# RHB0032E_pac.net
KiCad netlist of a schematic drawn in EAGLE
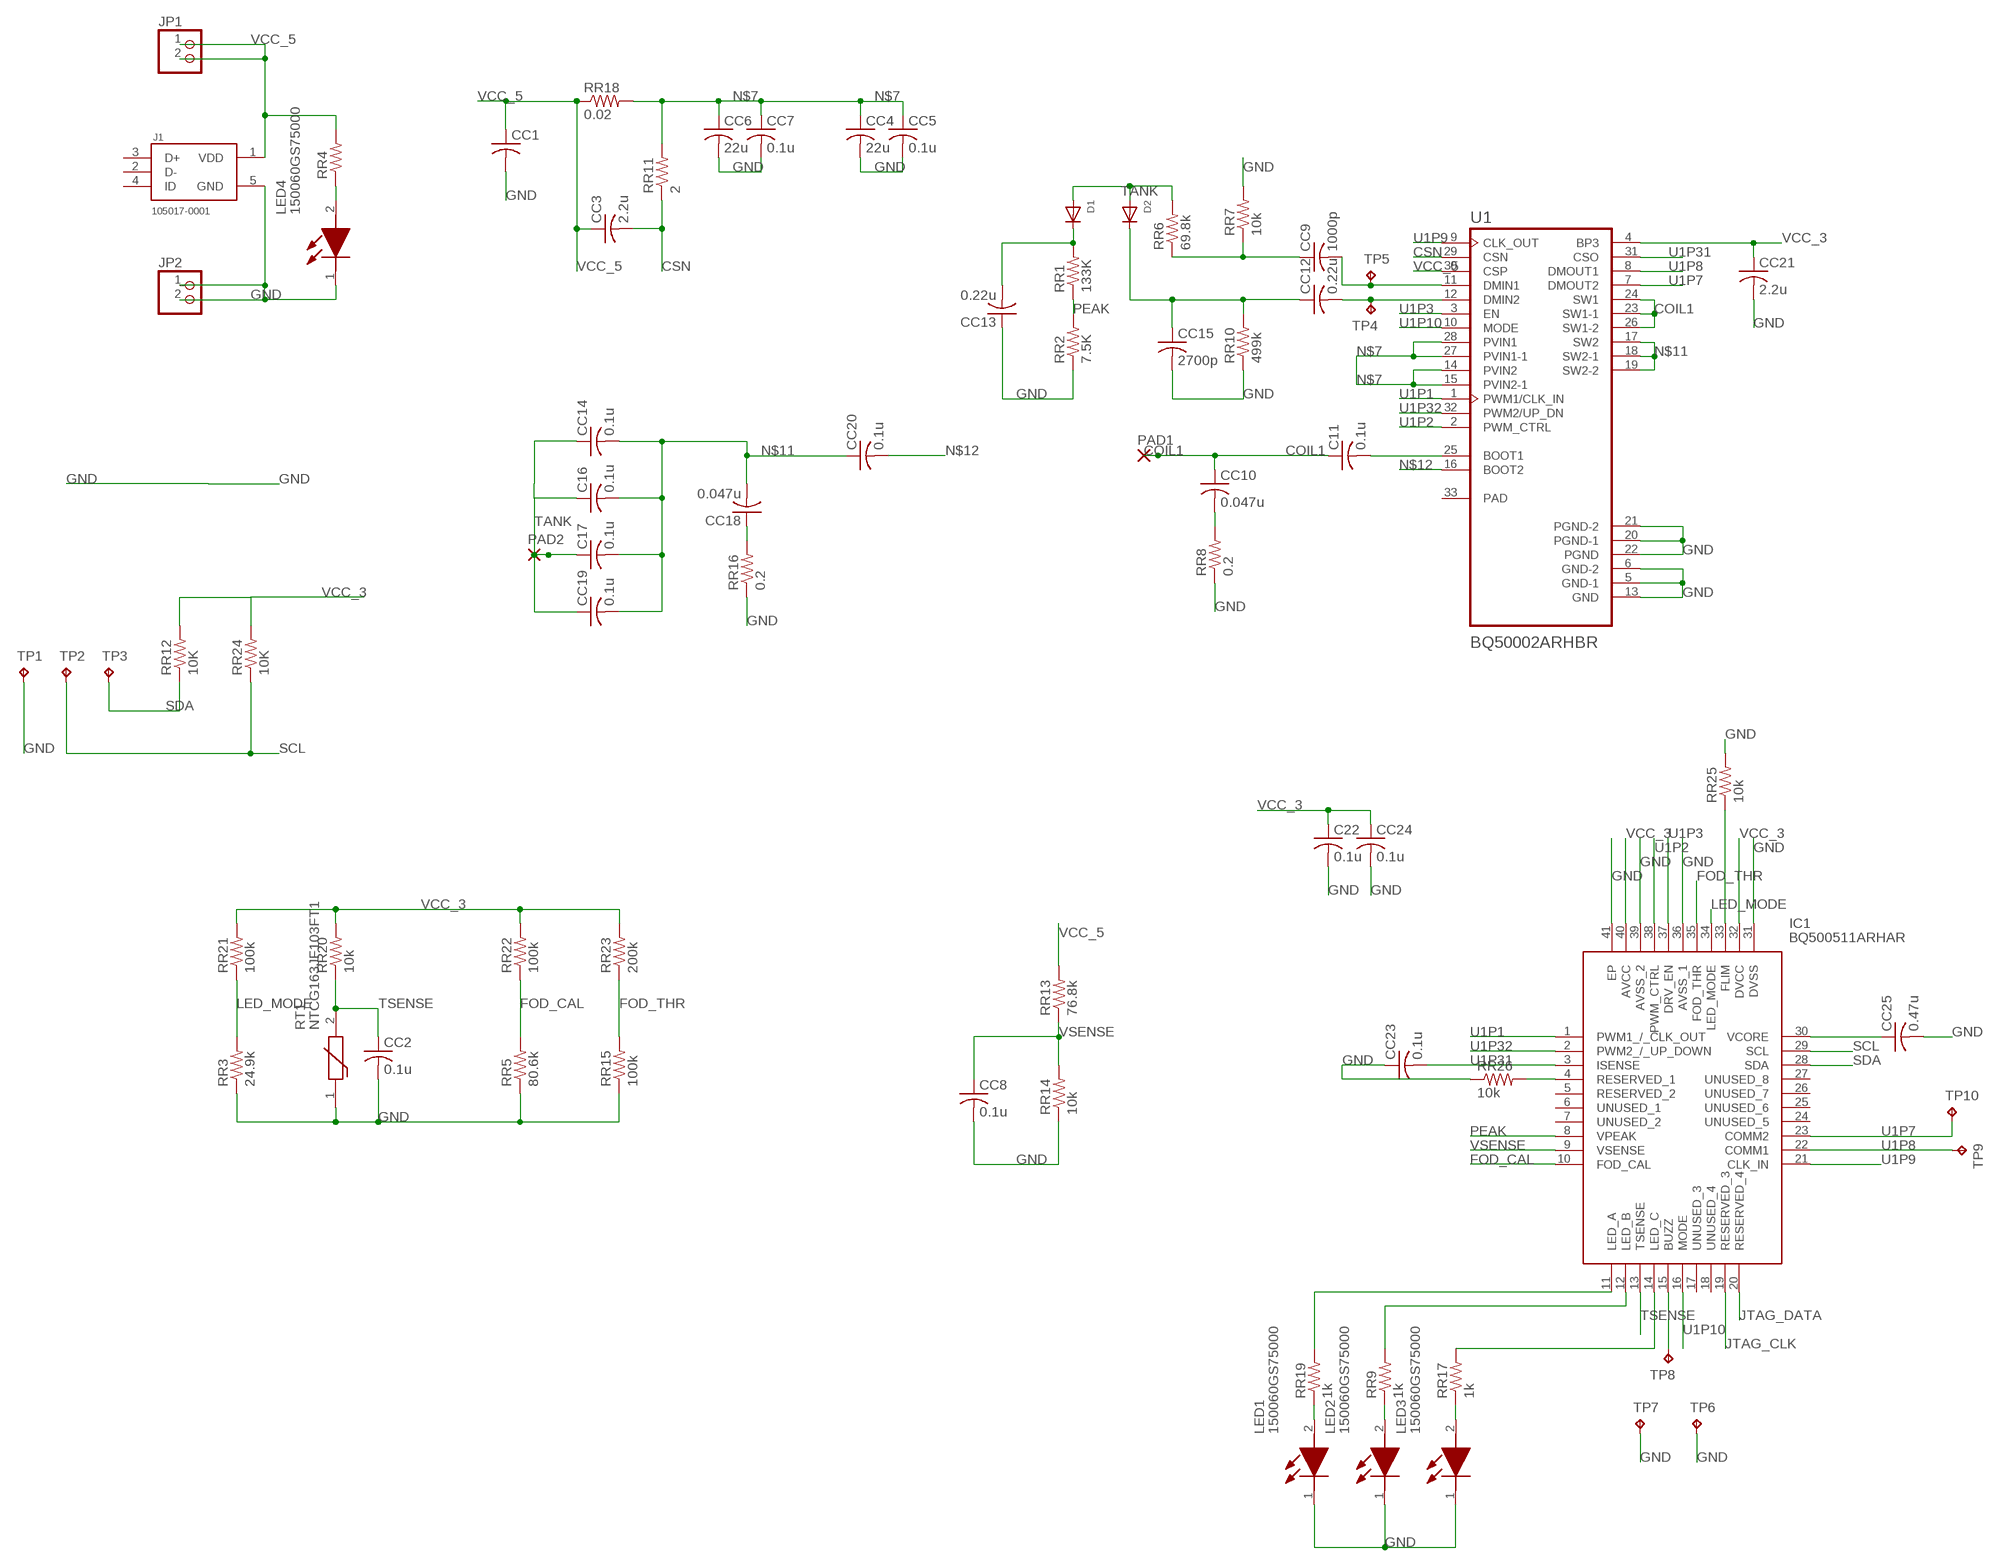
[diagram p0: schematic, sheet 1]

(export (version "E")
  (design (tool "Eeschema 10.0.6"))
  (components
    (comp (ref "C11")
      (value "0.1u")
      (footprint "eagle-import:C0402")
      (libsource (lib "eagle-import") (part "C-USC0402"))
    )
    (comp (ref "C16")
      (value "0.1u")
      (footprint "eagle-import:C0402")
      (libsource (lib "eagle-import") (part "C-USC0402"))
    )
    (comp (ref "C17")
      (value "0.1u")
      (footprint "eagle-import:C0402")
      (libsource (lib "eagle-import") (part "C-USC0402"))
    )
    (comp (ref "C22")
      (value "0.1u")
      (footprint "eagle-import:C0402")
      (libsource (lib "eagle-import") (part "C-USC0402"))
    )
    (comp (ref "CC1")
      (value "C-USC0402")
      (footprint "eagle-import:C0402")
      (libsource (lib "eagle-import") (part "C-USC0402"))
    )
    (comp (ref "CC2")
      (value "0.1u")
      (footprint "eagle-import:C0402")
      (libsource (lib "eagle-import") (part "C-USC0402"))
    )
    (comp (ref "CC3")
      (value "2.2u")
      (footprint "eagle-import:C0402")
      (libsource (lib "eagle-import") (part "C-USC0402"))
    )
    (comp (ref "CC4")
      (value "22u")
      (footprint "eagle-import:C0402")
      (libsource (lib "eagle-import") (part "C-USC0402"))
    )
    (comp (ref "CC5")
      (value "0.1u")
      (footprint "eagle-import:C0402")
      (libsource (lib "eagle-import") (part "C-USC0402"))
    )
    (comp (ref "CC6")
      (value "22u")
      (footprint "eagle-import:C0402")
      (libsource (lib "eagle-import") (part "C-USC0402"))
    )
    (comp (ref "CC7")
      (value "0.1u")
      (footprint "eagle-import:C0402")
      (libsource (lib "eagle-import") (part "C-USC0402"))
    )
    (comp (ref "CC8")
      (value "0.1u")
      (footprint "eagle-import:C0402")
      (libsource (lib "eagle-import") (part "C-USC0402"))
    )
    (comp (ref "CC9")
      (value "1000p")
      (footprint "eagle-import:C0402")
      (libsource (lib "eagle-import") (part "C-USC0402"))
    )
    (comp (ref "CC10")
      (value "0.047u")
      (footprint "eagle-import:C0402")
      (libsource (lib "eagle-import") (part "C-USC0402"))
    )
    (comp (ref "CC12")
      (value "0.22u")
      (footprint "eagle-import:C0402")
      (libsource (lib "eagle-import") (part "C-USC0402"))
    )
    (comp (ref "CC13")
      (value "0.22u")
      (footprint "eagle-import:C0402")
      (libsource (lib "eagle-import") (part "C-USC0402"))
    )
    (comp (ref "CC14")
      (value "0.1u")
      (footprint "eagle-import:C0402")
      (libsource (lib "eagle-import") (part "C-USC0402"))
    )
    (comp (ref "CC15")
      (value "2700p")
      (footprint "eagle-import:C0402")
      (libsource (lib "eagle-import") (part "C-USC0402"))
    )
    (comp (ref "CC18")
      (value "0.047u")
      (footprint "eagle-import:C0402")
      (libsource (lib "eagle-import") (part "C-USC0402"))
    )
    (comp (ref "CC19")
      (value "0.1u")
      (footprint "eagle-import:C0402")
      (libsource (lib "eagle-import") (part "C-USC0402"))
    )
    (comp (ref "CC20")
      (value "0.1u")
      (footprint "eagle-import:C0402")
      (libsource (lib "eagle-import") (part "C-USC0402"))
    )
    (comp (ref "CC21")
      (value "2.2u")
      (footprint "eagle-import:C0402")
      (libsource (lib "eagle-import") (part "C-USC0402"))
    )
    (comp (ref "CC23")
      (value "0.1u")
      (footprint "eagle-import:C0402")
      (libsource (lib "eagle-import") (part "C-USC0402"))
    )
    (comp (ref "CC24")
      (value "0.1u")
      (footprint "eagle-import:C0402")
      (libsource (lib "eagle-import") (part "C-USC0402"))
    )
    (comp (ref "CC25")
      (value "0.47u")
      (footprint "eagle-import:C0402")
      (libsource (lib "eagle-import") (part "C-USC0402"))
    )
    (comp (ref "D1")
      (value "DIODESOD-523")
      (footprint "eagle-import:SOD-523")
      (libsource (lib "eagle-import") (part "DIODESOD-523"))
    )
    (comp (ref "D2")
      (value "DIODESOD-523")
      (footprint "eagle-import:SOD-523")
      (libsource (lib "eagle-import") (part "DIODESOD-523"))
    )
    (comp (ref "IC1")
      (value "BQ500511ARHAR")
      (footprint "eagle-import:QFN50P600X600X100-41N")
      (fields (field (name "MOUSER_PART_NUMBER") "595-BQ500511ARHAR"))
      (libsource (lib "eagle-import") (part "BQ500511ARHAR"))
    )
    (comp (ref "J1")
      (value "105017-0001")
      (footprint "eagle-import:MOLEX_105017-0001")
      (fields (field (name "MF") "Molex"))
      (libsource (lib "eagle-import") (part "105017-0001"))
    )
    (comp (ref "JP1")
      (value "PINHD-1X2")
      (footprint "eagle-import:1X02")
      (libsource (lib "eagle-import") (part "PINHD-1X2"))
    )
    (comp (ref "JP2")
      (value "PINHD-1X2")
      (footprint "eagle-import:1X02")
      (libsource (lib "eagle-import") (part "PINHD-1X2"))
    )
    (comp (ref "LED1")
      (value "150060GS75000")
      (footprint "eagle-import:LEDC1608X80N")
      (fields (field (name "MOUSER_PART_NUMBER") "710-150060GS75000"))
      (libsource (lib "eagle-import") (part "150060GS75000"))
    )
    (comp (ref "LED2")
      (value "150060GS75000")
      (footprint "eagle-import:LEDC1608X80N")
      (fields (field (name "MOUSER_PART_NUMBER") "710-150060GS75000"))
      (libsource (lib "eagle-import") (part "150060GS75000"))
    )
    (comp (ref "LED3")
      (value "150060GS75000")
      (footprint "eagle-import:LEDC1608X80N")
      (fields (field (name "MOUSER_PART_NUMBER") "710-150060GS75000"))
      (libsource (lib "eagle-import") (part "150060GS75000"))
    )
    (comp (ref "LED4")
      (value "150060GS75000")
      (footprint "eagle-import:LEDC1608X80N")
      (fields (field (name "MOUSER_PART_NUMBER") "710-150060GS75000"))
      (libsource (lib "eagle-import") (part "150060GS75000"))
    )
    (comp (ref "PAD1")
      (value "SMD2")
      (footprint "eagle-import:SMD1,27-2,54")
      (libsource (lib "eagle-import") (part "SMD2"))
    )
    (comp (ref "PAD2")
      (value "SMD2")
      (footprint "eagle-import:SMD1,27-2,54")
      (libsource (lib "eagle-import") (part "SMD2"))
    )
    (comp (ref "RR1")
      (value "133K")
      (footprint "eagle-import:R0603")
      (libsource (lib "eagle-import") (part "R-US_R0603"))
    )
    (comp (ref "RR2")
      (value "7.5K")
      (footprint "eagle-import:R0603")
      (libsource (lib "eagle-import") (part "R-US_R0603"))
    )
    (comp (ref "RR3")
      (value "24.9k")
      (footprint "eagle-import:R0603")
      (libsource (lib "eagle-import") (part "R-US_R0603"))
    )
    (comp (ref "RR4")
      (value "R-US_R0603")
      (footprint "eagle-import:R0603")
      (libsource (lib "eagle-import") (part "R-US_R0603"))
    )
    (comp (ref "RR5")
      (value "80.6k")
      (footprint "eagle-import:R0603")
      (libsource (lib "eagle-import") (part "R-US_R0603"))
    )
    (comp (ref "RR6")
      (value "69.8k")
      (footprint "eagle-import:R0603")
      (libsource (lib "eagle-import") (part "R-US_R0603"))
    )
    (comp (ref "RR7")
      (value "10k")
      (footprint "eagle-import:R0603")
      (libsource (lib "eagle-import") (part "R-US_R0603"))
    )
    (comp (ref "RR8")
      (value "0.2")
      (footprint "eagle-import:R0603")
      (libsource (lib "eagle-import") (part "R-US_R0603"))
    )
    (comp (ref "RR9")
      (value "1k")
      (footprint "eagle-import:R0603")
      (libsource (lib "eagle-import") (part "R-US_R0603"))
    )
    (comp (ref "RR10")
      (value "499k")
      (footprint "eagle-import:R0603")
      (libsource (lib "eagle-import") (part "R-US_R0603"))
    )
    (comp (ref "RR11")
      (value "2")
      (footprint "eagle-import:R0603")
      (libsource (lib "eagle-import") (part "R-US_R0603"))
    )
    (comp (ref "RR12")
      (value "10K")
      (footprint "eagle-import:R0603")
      (libsource (lib "eagle-import") (part "R-US_R0603"))
    )
    (comp (ref "RR13")
      (value "76.8k")
      (footprint "eagle-import:R0603")
      (libsource (lib "eagle-import") (part "R-US_R0603"))
    )
    (comp (ref "RR14")
      (value "10k")
      (footprint "eagle-import:R0603")
      (libsource (lib "eagle-import") (part "R-US_R0603"))
    )
    (comp (ref "RR15")
      (value "100k")
      (footprint "eagle-import:R0603")
      (libsource (lib "eagle-import") (part "R-US_R0603"))
    )
    (comp (ref "RR16")
      (value "0.2")
      (footprint "eagle-import:R0603")
      (libsource (lib "eagle-import") (part "R-US_R0603"))
    )
    (comp (ref "RR17")
      (value "1k")
      (footprint "eagle-import:R0603")
      (libsource (lib "eagle-import") (part "R-US_R0603"))
    )
    (comp (ref "RR18")
      (value "0.02")
      (footprint "eagle-import:R0603")
      (libsource (lib "eagle-import") (part "R-US_R0603"))
    )
    (comp (ref "RR19")
      (value "1k")
      (footprint "eagle-import:R0603")
      (libsource (lib "eagle-import") (part "R-US_R0603"))
    )
    (comp (ref "RR20")
      (value "10k")
      (footprint "eagle-import:R0603")
      (libsource (lib "eagle-import") (part "R-US_R0603"))
    )
    (comp (ref "RR21")
      (value "100k")
      (footprint "eagle-import:R0603")
      (libsource (lib "eagle-import") (part "R-US_R0603"))
    )
    (comp (ref "RR22")
      (value "100k")
      (footprint "eagle-import:R0603")
      (libsource (lib "eagle-import") (part "R-US_R0603"))
    )
    (comp (ref "RR23")
      (value "200k")
      (footprint "eagle-import:R0603")
      (libsource (lib "eagle-import") (part "R-US_R0603"))
    )
    (comp (ref "RR24")
      (value "10K")
      (footprint "eagle-import:R0603")
      (libsource (lib "eagle-import") (part "R-US_R0603"))
    )
    (comp (ref "RR25")
      (value "10k")
      (footprint "eagle-import:R0603")
      (libsource (lib "eagle-import") (part "R-US_R0603"))
    )
    (comp (ref "RR26")
      (value "10k")
      (footprint "eagle-import:R0603")
      (libsource (lib "eagle-import") (part "R-US_R0603"))
    )
    (comp (ref "RT1")
      (value "NTCG163JF103FT1")
      (footprint "eagle-import:THRMC1608X90N")
      (fields (field (name "MOUSER_PART_NUMBER") "810-NTCG163JF103FT1"))
      (libsource (lib "eagle-import") (part "NTCG163JF103FT1"))
    )
    (comp (ref "TP1")
      (value "TPB1,27")
      (footprint "eagle-import:B1,27")
      (libsource (lib "eagle-import") (part "TPB1,27"))
    )
    (comp (ref "TP2")
      (value "TPB1,27")
      (footprint "eagle-import:B1,27")
      (libsource (lib "eagle-import") (part "TPB1,27"))
    )
    (comp (ref "TP3")
      (value "TPB1,27")
      (footprint "eagle-import:B1,27")
      (libsource (lib "eagle-import") (part "TPB1,27"))
    )
    (comp (ref "TP4")
      (value "TPB1,27")
      (footprint "eagle-import:B1,27")
      (libsource (lib "eagle-import") (part "TPB1,27"))
    )
    (comp (ref "TP5")
      (value "TPB1,27")
      (footprint "eagle-import:B1,27")
      (libsource (lib "eagle-import") (part "TPB1,27"))
    )
    (comp (ref "TP6")
      (value "TPB1,27")
      (footprint "eagle-import:B1,27")
      (libsource (lib "eagle-import") (part "TPB1,27"))
    )
    (comp (ref "TP7")
      (value "TPB1,27")
      (footprint "eagle-import:B1,27")
      (libsource (lib "eagle-import") (part "TPB1,27"))
    )
    (comp (ref "TP8")
      (value "TPB1,27")
      (footprint "eagle-import:B1,27")
      (libsource (lib "eagle-import") (part "TPB1,27"))
    )
    (comp (ref "TP9")
      (value "TPB1,27")
      (footprint "eagle-import:B1,27")
      (libsource (lib "eagle-import") (part "TPB1,27"))
    )
    (comp (ref "TP10")
      (value "TPB1,27")
      (footprint "eagle-import:B1,27")
      (libsource (lib "eagle-import") (part "TPB1,27"))
    )
    (comp (ref "U1")
      (value "BQ50002ARHBR")
      (footprint "eagle-import:IC_ADS125H01IRHBT")
      (fields (field (name "MF") "Texas Instruments"))
      (libsource (lib "eagle-import") (part "BQ50002ARHBR"))
    )
  )
  (nets
    (net (code "1") (name "/COIL1") (class "Default")
      (node (ref "C11") (pin "1") (pinfunction "1_1") (pintype "passive"))
      (node (ref "CC10") (pin "1") (pinfunction "1_1") (pintype "passive"))
      (node (ref "PAD1") (pin "1") (pinfunction "P_1") (pintype "passive"))
      (node (ref "U1") (pin "23") (pinfunction "SW1-1_23") (pintype "output"))
      (node (ref "U1") (pin "24") (pinfunction "SW1_24") (pintype "output"))
      (node (ref "U1") (pin "26") (pinfunction "SW1-2_26") (pintype "output"))
    )
    (net (code "2") (name "/CSN") (class "Default")
      (node (ref "CC3") (pin "2") (pinfunction "2_2") (pintype "passive"))
      (node (ref "RR11") (pin "1") (pinfunction "1_1") (pintype "passive"))
      (node (ref "U1") (pin "29") (pinfunction "CSN_29") (pintype "input"))
    )
    (net (code "3") (name "/FOD_CAL") (class "Default")
      (node (ref "IC1") (pin "10") (pinfunction "FOD_CAL_10") (pintype "bidirectional"))
      (node (ref "RR22") (pin "1") (pinfunction "1_1") (pintype "passive"))
      (node (ref "RR5") (pin "2") (pinfunction "2_2") (pintype "passive"))
    )
    (net (code "4") (name "/FOD_THR") (class "Default")
      (node (ref "IC1") (pin "35") (pinfunction "FOD_THR_35") (pintype "bidirectional"))
      (node (ref "RR15") (pin "2") (pinfunction "2_2") (pintype "passive"))
      (node (ref "RR23") (pin "1") (pinfunction "1_1") (pintype "passive"))
    )
    (net (code "5") (name "/GND") (class "Default")
      (node (ref "C22") (pin "2") (pinfunction "2_2") (pintype "passive"))
      (node (ref "CC1") (pin "2") (pinfunction "2_2") (pintype "passive"))
      (node (ref "CC13") (pin "1") (pinfunction "1_1") (pintype "passive"))
      (node (ref "CC15") (pin "2") (pinfunction "2_2") (pintype "passive"))
      (node (ref "CC2") (pin "2") (pinfunction "2_2") (pintype "passive"))
      (node (ref "CC21") (pin "2") (pinfunction "2_2") (pintype "passive"))
      (node (ref "CC23") (pin "1") (pinfunction "1_1") (pintype "passive"))
      (node (ref "CC24") (pin "2") (pinfunction "2_2") (pintype "passive"))
      (node (ref "CC25") (pin "2") (pinfunction "2_2") (pintype "passive"))
      (node (ref "CC4") (pin "2") (pinfunction "2_2") (pintype "passive"))
      (node (ref "CC5") (pin "2") (pinfunction "2_2") (pintype "passive"))
      (node (ref "CC6") (pin "2") (pinfunction "2_2") (pintype "passive"))
      (node (ref "CC7") (pin "2") (pinfunction "2_2") (pintype "passive"))
      (node (ref "CC8") (pin "2") (pinfunction "2_2") (pintype "passive"))
      (node (ref "IC1") (pin "31") (pinfunction "DVSS_31") (pintype "bidirectional"))
      (node (ref "IC1") (pin "36") (pinfunction "AVSS_1_36") (pintype "bidirectional"))
      (node (ref "IC1") (pin "39") (pinfunction "AVSS_2_39") (pintype "bidirectional"))
      (node (ref "IC1") (pin "41") (pinfunction "EP_41") (pintype "bidirectional"))
      (node (ref "J1") (pin "5") (pinfunction "GND_5") (pintype "power_in"))
      (node (ref "JP2") (pin "1") (pinfunction "1_1") (pintype "passive"))
      (node (ref "JP2") (pin "2") (pinfunction "2_2") (pintype "passive"))
      (node (ref "LED1") (pin "1") (pinfunction "K_1") (pintype "bidirectional"))
      (node (ref "LED2") (pin "1") (pinfunction "K_1") (pintype "bidirectional"))
      (node (ref "LED3") (pin "1") (pinfunction "K_1") (pintype "bidirectional"))
      (node (ref "LED4") (pin "1") (pinfunction "K_1") (pintype "bidirectional"))
      (node (ref "RR10") (pin "1") (pinfunction "1_1") (pintype "passive"))
      (node (ref "RR14") (pin "1") (pinfunction "1_1") (pintype "passive"))
      (node (ref "RR15") (pin "1") (pinfunction "1_1") (pintype "passive"))
      (node (ref "RR16") (pin "1") (pinfunction "1_1") (pintype "passive"))
      (node (ref "RR2") (pin "1") (pinfunction "1_1") (pintype "passive"))
      (node (ref "RR25") (pin "2") (pinfunction "2_2") (pintype "passive"))
      (node (ref "RR26") (pin "1") (pinfunction "1_1") (pintype "passive"))
      (node (ref "RR3") (pin "1") (pinfunction "1_1") (pintype "passive"))
      (node (ref "RR5") (pin "1") (pinfunction "1_1") (pintype "passive"))
      (node (ref "RR7") (pin "2") (pinfunction "2_2") (pintype "passive"))
      (node (ref "RR8") (pin "1") (pinfunction "1_1") (pintype "passive"))
      (node (ref "RT1") (pin "1") (pinfunction "1_1") (pintype "bidirectional"))
      (node (ref "TP1") (pin "TP") (pinfunction "TP_TP") (pintype "input"))
      (node (ref "TP6") (pin "TP") (pinfunction "TP_TP") (pintype "input"))
      (node (ref "TP7") (pin "TP") (pinfunction "TP_TP") (pintype "input"))
      (node (ref "U1") (pin "13") (pinfunction "GND_13") (pintype "power_in"))
      (node (ref "U1") (pin "20") (pinfunction "PGND-1_20") (pintype "power_in"))
      (node (ref "U1") (pin "21") (pinfunction "PGND-2_21") (pintype "power_in"))
      (node (ref "U1") (pin "22") (pinfunction "PGND_22") (pintype "power_in"))
      (node (ref "U1") (pin "5") (pinfunction "GND-1_5") (pintype "power_in"))
      (node (ref "U1") (pin "6") (pinfunction "GND-2_6") (pintype "power_in"))
    )
    (net (code "6") (name "/JTAG_CLK") (class "Default")
      (node (ref "IC1") (pin "19") (pinfunction "RESERVED_3_19") (pintype "bidirectional"))
    )
    (net (code "7") (name "/JTAG_DATA") (class "Default")
      (node (ref "IC1") (pin "20") (pinfunction "RESERVED_4_20") (pintype "bidirectional"))
    )
    (net (code "8") (name "/LED_MODE") (class "Default")
      (node (ref "IC1") (pin "34") (pinfunction "LED_MODE_34") (pintype "bidirectional"))
      (node (ref "RR21") (pin "1") (pinfunction "1_1") (pintype "passive"))
      (node (ref "RR3") (pin "2") (pinfunction "2_2") (pintype "passive"))
    )
    (net (code "9") (name "/N$7") (class "Default")
      (node (ref "CC4") (pin "1") (pinfunction "1_1") (pintype "passive"))
      (node (ref "CC5") (pin "1") (pinfunction "1_1") (pintype "passive"))
      (node (ref "CC6") (pin "1") (pinfunction "1_1") (pintype "passive"))
      (node (ref "CC7") (pin "1") (pinfunction "1_1") (pintype "passive"))
      (node (ref "RR11") (pin "2") (pinfunction "2_2") (pintype "passive"))
      (node (ref "RR18") (pin "2") (pinfunction "2_2") (pintype "passive"))
      (node (ref "U1") (pin "14") (pinfunction "PVIN2_14") (pintype "input"))
      (node (ref "U1") (pin "15") (pinfunction "PVIN2-1_15") (pintype "input"))
      (node (ref "U1") (pin "27") (pinfunction "PVIN1-1_27") (pintype "input"))
      (node (ref "U1") (pin "28") (pinfunction "PVIN1_28") (pintype "input"))
    )
    (net (code "10") (name "/N$11") (class "Default")
      (node (ref "C16") (pin "2") (pinfunction "2_2") (pintype "passive"))
      (node (ref "C17") (pin "2") (pinfunction "2_2") (pintype "passive"))
      (node (ref "CC14") (pin "2") (pinfunction "2_2") (pintype "passive"))
      (node (ref "CC18") (pin "2") (pinfunction "2_2") (pintype "passive"))
      (node (ref "CC19") (pin "2") (pinfunction "2_2") (pintype "passive"))
      (node (ref "CC20") (pin "1") (pinfunction "1_1") (pintype "passive"))
      (node (ref "U1") (pin "17") (pinfunction "SW2_17") (pintype "output"))
      (node (ref "U1") (pin "18") (pinfunction "SW2-1_18") (pintype "output"))
      (node (ref "U1") (pin "19") (pinfunction "SW2-2_19") (pintype "output"))
    )
    (net (code "11") (name "/N$12") (class "Default")
      (node (ref "CC20") (pin "2") (pinfunction "2_2") (pintype "passive"))
      (node (ref "U1") (pin "16") (pinfunction "BOOT2_16") (pintype "bidirectional"))
    )
    (net (code "12") (name "/PEAK") (class "Default")
      (node (ref "IC1") (pin "8") (pinfunction "VPEAK_8") (pintype "bidirectional"))
      (node (ref "RR1") (pin "1") (pinfunction "1_1") (pintype "passive"))
      (node (ref "RR2") (pin "2") (pinfunction "2_2") (pintype "passive"))
    )
    (net (code "13") (name "/SCL") (class "Default")
      (node (ref "IC1") (pin "29") (pinfunction "SCL_29") (pintype "bidirectional"))
      (node (ref "RR24") (pin "1") (pinfunction "1_1") (pintype "passive"))
      (node (ref "TP2") (pin "TP") (pinfunction "TP_TP") (pintype "input"))
    )
    (net (code "14") (name "/SDA") (class "Default")
      (node (ref "IC1") (pin "28") (pinfunction "SDA_28") (pintype "bidirectional"))
      (node (ref "RR12") (pin "1") (pinfunction "1_1") (pintype "passive"))
      (node (ref "TP3") (pin "TP") (pinfunction "TP_TP") (pintype "input"))
    )
    (net (code "15") (name "/TANK") (class "Default")
      (node (ref "C16") (pin "1") (pinfunction "1_1") (pintype "passive"))
      (node (ref "C17") (pin "1") (pinfunction "1_1") (pintype "passive"))
      (node (ref "CC14") (pin "1") (pinfunction "1_1") (pintype "passive"))
      (node (ref "CC19") (pin "1") (pinfunction "1_1") (pintype "passive"))
      (node (ref "D1") (pin "A") (pinfunction "A_A") (pintype "passive"))
      (node (ref "D2") (pin "A") (pinfunction "A_A") (pintype "passive"))
      (node (ref "PAD2") (pin "1") (pinfunction "P_1") (pintype "passive"))
      (node (ref "RR6") (pin "2") (pinfunction "2_2") (pintype "passive"))
    )
    (net (code "16") (name "/TSENSE") (class "Default")
      (node (ref "CC2") (pin "1") (pinfunction "1_1") (pintype "passive"))
      (node (ref "IC1") (pin "13") (pinfunction "TSENSE_13") (pintype "bidirectional"))
      (node (ref "RR20") (pin "1") (pinfunction "1_1") (pintype "passive"))
      (node (ref "RT1") (pin "2") (pinfunction "2_2") (pintype "bidirectional"))
    )
    (net (code "17") (name "/U1P1") (class "Default")
      (node (ref "IC1") (pin "1") (pinfunction "PWM1_/_CLK_OUT_1") (pintype "bidirectional"))
      (node (ref "U1") (pin "1") (pinfunction "PWM1/CLK_IN_1") (pintype "input"))
    )
    (net (code "18") (name "/U1P2") (class "Default")
      (node (ref "IC1") (pin "38") (pinfunction "PWM_CTRL_38") (pintype "bidirectional"))
      (node (ref "U1") (pin "2") (pinfunction "PWM_CTRL_2") (pintype "input"))
    )
    (net (code "19") (name "/U1P3") (class "Default")
      (node (ref "IC1") (pin "37") (pinfunction "DRV_EN_37") (pintype "bidirectional"))
      (node (ref "U1") (pin "3") (pinfunction "EN_3") (pintype "input"))
    )
    (net (code "20") (name "/U1P7") (class "Default")
      (node (ref "IC1") (pin "23") (pinfunction "COMM2_23") (pintype "bidirectional"))
      (node (ref "TP10") (pin "TP") (pinfunction "TP_TP") (pintype "input"))
      (node (ref "U1") (pin "7") (pinfunction "DMOUT2_7") (pintype "output"))
    )
    (net (code "21") (name "/U1P8") (class "Default")
      (node (ref "IC1") (pin "22") (pinfunction "COMM1_22") (pintype "bidirectional"))
      (node (ref "TP9") (pin "TP") (pinfunction "TP_TP") (pintype "input"))
      (node (ref "U1") (pin "8") (pinfunction "DMOUT1_8") (pintype "output"))
    )
    (net (code "22") (name "/U1P9") (class "Default")
      (node (ref "IC1") (pin "21") (pinfunction "CLK_IN_21") (pintype "bidirectional"))
      (node (ref "U1") (pin "9") (pinfunction "CLK_OUT_9") (pintype "input"))
    )
    (net (code "23") (name "/U1P10") (class "Default")
      (node (ref "IC1") (pin "16") (pinfunction "MODE_16") (pintype "bidirectional"))
      (node (ref "U1") (pin "10") (pinfunction "MODE_10") (pintype "input"))
    )
    (net (code "24") (name "/U1P31") (class "Default")
      (node (ref "CC23") (pin "2") (pinfunction "2_2") (pintype "passive"))
      (node (ref "IC1") (pin "3") (pinfunction "ISENSE_3") (pintype "bidirectional"))
      (node (ref "U1") (pin "31") (pinfunction "CSO_31") (pintype "output"))
    )
    (net (code "25") (name "/U1P32") (class "Default")
      (node (ref "IC1") (pin "2") (pinfunction "PWM2_/_UP_DOWN_2") (pintype "bidirectional"))
      (node (ref "U1") (pin "32") (pinfunction "PWM2/UP_DN_32") (pintype "input"))
    )
    (net (code "26") (name "/VCC_3") (class "Default")
      (node (ref "C22") (pin "1") (pinfunction "1_1") (pintype "passive"))
      (node (ref "CC21") (pin "1") (pinfunction "1_1") (pintype "passive"))
      (node (ref "CC24") (pin "1") (pinfunction "1_1") (pintype "passive"))
      (node (ref "IC1") (pin "32") (pinfunction "DVCC_32") (pintype "bidirectional"))
      (node (ref "IC1") (pin "40") (pinfunction "AVCC_40") (pintype "bidirectional"))
      (node (ref "RR12") (pin "2") (pinfunction "2_2") (pintype "passive"))
      (node (ref "RR20") (pin "2") (pinfunction "2_2") (pintype "passive"))
      (node (ref "RR21") (pin "2") (pinfunction "2_2") (pintype "passive"))
      (node (ref "RR22") (pin "2") (pinfunction "2_2") (pintype "passive"))
      (node (ref "RR23") (pin "2") (pinfunction "2_2") (pintype "passive"))
      (node (ref "RR24") (pin "2") (pinfunction "2_2") (pintype "passive"))
      (node (ref "U1") (pin "4") (pinfunction "BP3_4") (pintype "output"))
    )
    (net (code "27") (name "/VCC_5") (class "Default")
      (node (ref "CC1") (pin "1") (pinfunction "1_1") (pintype "passive"))
      (node (ref "CC3") (pin "1") (pinfunction "1_1") (pintype "passive"))
      (node (ref "J1") (pin "1") (pinfunction "VDD_1") (pintype "power_in"))
      (node (ref "JP1") (pin "1") (pinfunction "1_1") (pintype "passive"))
      (node (ref "JP1") (pin "2") (pinfunction "2_2") (pintype "passive"))
      (node (ref "RR13") (pin "2") (pinfunction "2_2") (pintype "passive"))
      (node (ref "RR18") (pin "1") (pinfunction "1_1") (pintype "passive"))
      (node (ref "RR4") (pin "2") (pinfunction "2_2") (pintype "passive"))
      (node (ref "U1") (pin "30") (pinfunction "CSP_30") (pintype "input"))
    )
    (net (code "28") (name "/VSENSE") (class "Default")
      (node (ref "CC8") (pin "1") (pinfunction "1_1") (pintype "passive"))
      (node (ref "IC1") (pin "9") (pinfunction "VSENSE_9") (pintype "bidirectional"))
      (node (ref "RR13") (pin "1") (pinfunction "1_1") (pintype "passive"))
      (node (ref "RR14") (pin "2") (pinfunction "2_2") (pintype "passive"))
    )
    (net (code "29") (name "Net-(CC9-Pad1)") (class "Default")
      (node (ref "CC9") (pin "1") (pinfunction "1_1") (pintype "passive"))
      (node (ref "RR6") (pin "1") (pinfunction "1_1") (pintype "passive"))
      (node (ref "RR7") (pin "1") (pinfunction "1_1") (pintype "passive"))
    )
    (net (code "30") (name "Net-(CC10-Pad2)") (class "Default")
      (node (ref "CC10") (pin "2") (pinfunction "2_2") (pintype "passive"))
      (node (ref "RR8") (pin "2") (pinfunction "2_2") (pintype "passive"))
    )
    (net (code "31") (name "Net-(CC18-Pad1)") (class "Default")
      (node (ref "CC18") (pin "1") (pinfunction "1_1") (pintype "passive"))
      (node (ref "RR16") (pin "2") (pinfunction "2_2") (pintype "passive"))
    )
    (net (code "32") (name "Net-(D1-C)") (class "Default")
      (node (ref "CC13") (pin "2") (pinfunction "2_2") (pintype "passive"))
      (node (ref "D1") (pin "K") (pinfunction "C_K") (pintype "passive"))
      (node (ref "RR1") (pin "2") (pinfunction "2_2") (pintype "passive"))
    )
    (net (code "33") (name "Net-(D2-C)") (class "Default")
      (node (ref "CC12") (pin "1") (pinfunction "1_1") (pintype "passive"))
      (node (ref "CC15") (pin "1") (pinfunction "1_1") (pintype "passive"))
      (node (ref "D2") (pin "K") (pinfunction "C_K") (pintype "passive"))
      (node (ref "RR10") (pin "2") (pinfunction "2_2") (pintype "passive"))
    )
    (net (code "34") (name "Net-(IC1-BUZZ)") (class "Default")
      (node (ref "IC1") (pin "15") (pinfunction "BUZZ_15") (pintype "bidirectional"))
      (node (ref "TP8") (pin "TP") (pinfunction "TP_TP") (pintype "input"))
    )
    (net (code "35") (name "Net-(IC1-FLIM)") (class "Default")
      (node (ref "IC1") (pin "33") (pinfunction "FLIM_33") (pintype "bidirectional"))
      (node (ref "RR25") (pin "1") (pinfunction "1_1") (pintype "passive"))
    )
    (net (code "36") (name "Net-(IC1-LED_A)") (class "Default")
      (node (ref "IC1") (pin "11") (pinfunction "LED_A_11") (pintype "bidirectional"))
      (node (ref "RR19") (pin "2") (pinfunction "2_2") (pintype "passive"))
    )
    (net (code "37") (name "Net-(IC1-LED_B)") (class "Default")
      (node (ref "IC1") (pin "12") (pinfunction "LED_B_12") (pintype "bidirectional"))
      (node (ref "RR9") (pin "2") (pinfunction "2_2") (pintype "passive"))
    )
    (net (code "38") (name "Net-(IC1-LED_C)") (class "Default")
      (node (ref "IC1") (pin "14") (pinfunction "LED_C_14") (pintype "bidirectional"))
      (node (ref "RR17") (pin "2") (pinfunction "2_2") (pintype "passive"))
    )
    (net (code "39") (name "Net-(IC1-RESERVED_1)") (class "Default")
      (node (ref "IC1") (pin "4") (pinfunction "RESERVED_1_4") (pintype "bidirectional"))
      (node (ref "RR26") (pin "2") (pinfunction "2_2") (pintype "passive"))
    )
    (net (code "40") (name "Net-(IC1-VCORE)") (class "Default")
      (node (ref "CC25") (pin "1") (pinfunction "1_1") (pintype "passive"))
      (node (ref "IC1") (pin "30") (pinfunction "VCORE_30") (pintype "bidirectional"))
    )
    (net (code "41") (name "Net-(LED1-A)") (class "Default")
      (node (ref "LED1") (pin "2") (pinfunction "A_2") (pintype "bidirectional"))
      (node (ref "RR19") (pin "1") (pinfunction "1_1") (pintype "passive"))
    )
    (net (code "42") (name "Net-(LED2-A)") (class "Default")
      (node (ref "LED2") (pin "2") (pinfunction "A_2") (pintype "bidirectional"))
      (node (ref "RR9") (pin "1") (pinfunction "1_1") (pintype "passive"))
    )
    (net (code "43") (name "Net-(LED3-A)") (class "Default")
      (node (ref "LED3") (pin "2") (pinfunction "A_2") (pintype "bidirectional"))
      (node (ref "RR17") (pin "1") (pinfunction "1_1") (pintype "passive"))
    )
    (net (code "44") (name "Net-(LED4-A)") (class "Default")
      (node (ref "LED4") (pin "2") (pinfunction "A_2") (pintype "bidirectional"))
      (node (ref "RR4") (pin "1") (pinfunction "1_1") (pintype "passive"))
    )
    (net (code "45") (name "Net-(U1-BOOT1)") (class "Default")
      (node (ref "C11") (pin "2") (pinfunction "2_2") (pintype "passive"))
      (node (ref "U1") (pin "25") (pinfunction "BOOT1_25") (pintype "bidirectional"))
    )
    (net (code "46") (name "Net-(U1-DMIN1)") (class "Default")
      (node (ref "CC9") (pin "2") (pinfunction "2_2") (pintype "passive"))
      (node (ref "TP5") (pin "TP") (pinfunction "TP_TP") (pintype "input"))
      (node (ref "U1") (pin "11") (pinfunction "DMIN1_11") (pintype "input"))
    )
    (net (code "47") (name "Net-(U1-DMIN2)") (class "Default")
      (node (ref "CC12") (pin "2") (pinfunction "2_2") (pintype "passive"))
      (node (ref "TP4") (pin "TP") (pinfunction "TP_TP") (pintype "input"))
      (node (ref "U1") (pin "12") (pinfunction "DMIN2_12") (pintype "input"))
    )
    (net (code "48") (name "unconnected-(IC1-RESERVED_2-Pad5)") (class "Default")
      (node (ref "IC1") (pin "5") (pinfunction "RESERVED_2_5") (pintype "bidirectional"))
    )
    (net (code "49") (name "unconnected-(IC1-UNUSED_1-Pad6)") (class "Default")
      (node (ref "IC1") (pin "6") (pinfunction "UNUSED_1_6") (pintype "bidirectional"))
    )
    (net (code "50") (name "unconnected-(IC1-UNUSED_2-Pad7)") (class "Default")
      (node (ref "IC1") (pin "7") (pinfunction "UNUSED_2_7") (pintype "bidirectional"))
    )
    (net (code "51") (name "unconnected-(IC1-UNUSED_3-Pad17)") (class "Default")
      (node (ref "IC1") (pin "17") (pinfunction "UNUSED_3_17") (pintype "bidirectional"))
    )
    (net (code "52") (name "unconnected-(IC1-UNUSED_4-Pad18)") (class "Default")
      (node (ref "IC1") (pin "18") (pinfunction "UNUSED_4_18") (pintype "bidirectional"))
    )
    (net (code "53") (name "unconnected-(IC1-UNUSED_5-Pad24)") (class "Default")
      (node (ref "IC1") (pin "24") (pinfunction "UNUSED_5_24") (pintype "bidirectional"))
    )
    (net (code "54") (name "unconnected-(IC1-UNUSED_6-Pad25)") (class "Default")
      (node (ref "IC1") (pin "25") (pinfunction "UNUSED_6_25") (pintype "bidirectional"))
    )
    (net (code "55") (name "unconnected-(IC1-UNUSED_7-Pad26)") (class "Default")
      (node (ref "IC1") (pin "26") (pinfunction "UNUSED_7_26") (pintype "bidirectional"))
    )
    (net (code "56") (name "unconnected-(IC1-UNUSED_8-Pad27)") (class "Default")
      (node (ref "IC1") (pin "27") (pinfunction "UNUSED_8_27") (pintype "bidirectional"))
    )
    (net (code "57") (name "unconnected-(J1-D+-Pad3)") (class "Default")
      (node (ref "J1") (pin "3") (pinfunction "D+_3") (pintype "bidirectional"))
    )
    (net (code "58") (name "unconnected-(J1-D--Pad2)") (class "Default")
      (node (ref "J1") (pin "2") (pinfunction "D-_2") (pintype "bidirectional"))
    )
    (net (code "59") (name "unconnected-(J1-ID-Pad4)") (class "Default")
      (node (ref "J1") (pin "4") (pinfunction "ID_4") (pintype "passive"))
    )
    (net (code "60") (name "unconnected-(U1-PAD-Pad33)") (class "Default")
      (node (ref "U1") (pin "33") (pinfunction "PAD_33") (pintype "bidirectional"))
    )
  )
)
